# ROCKCHIP_PWR_SUPPLY.net
KiCad netlist of a schematic drawn in Altium Designer
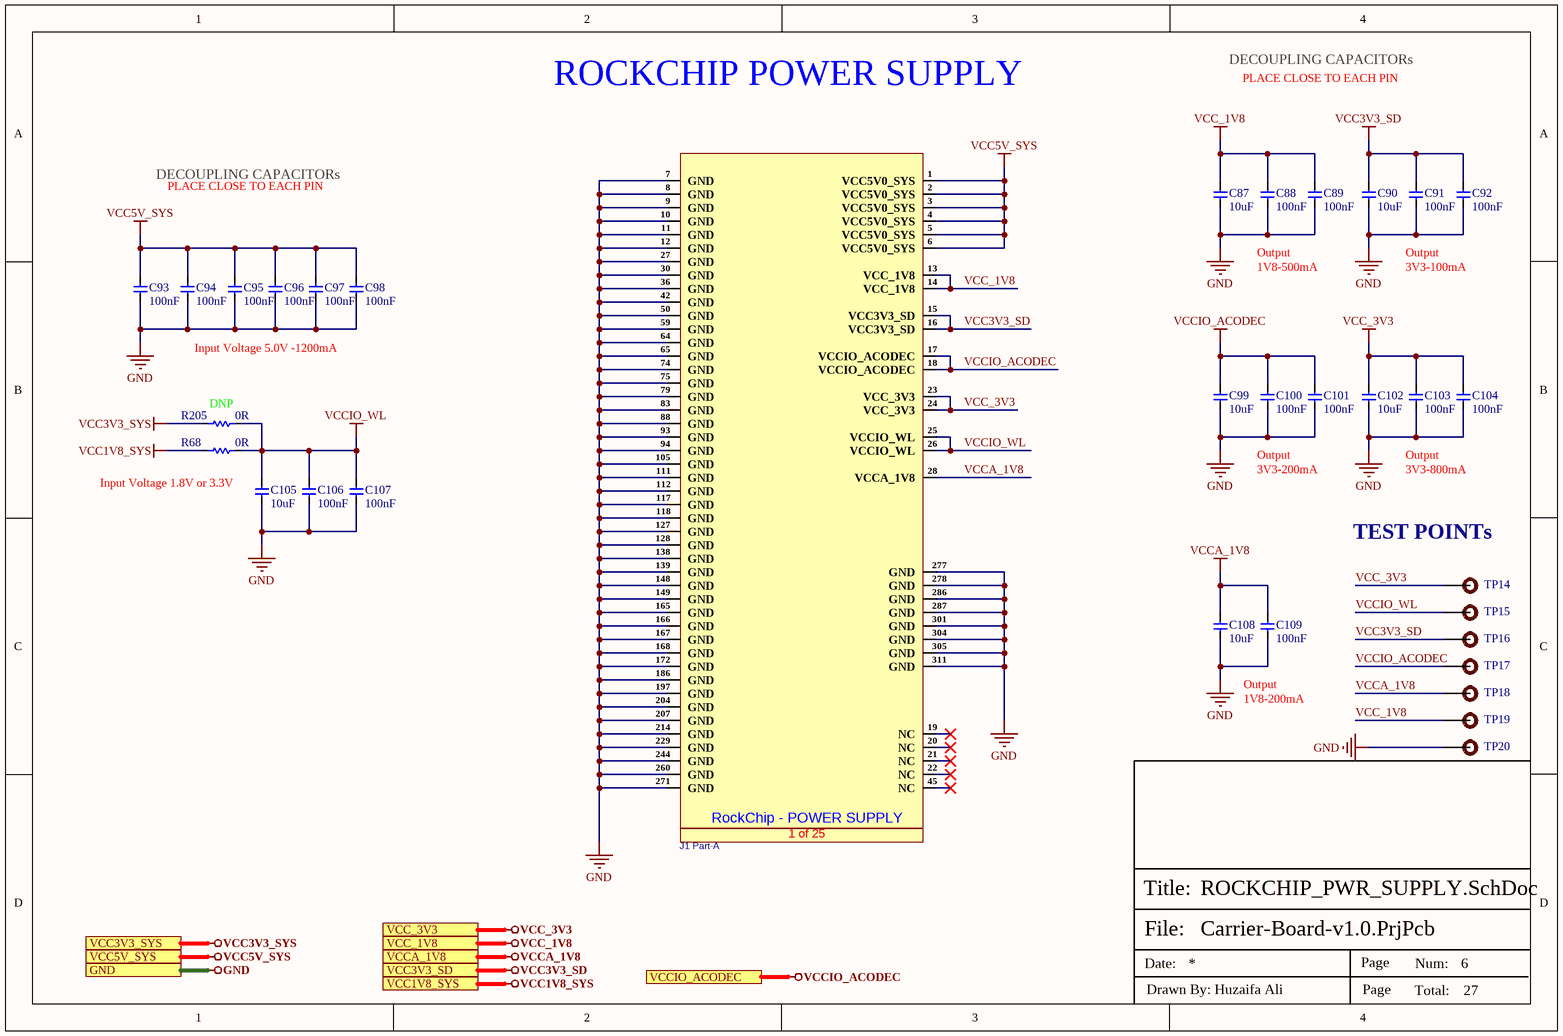
[diagram p0: ROCKCHIP_PWR_SUPPLY.SchDoc]

(export (version "E")
  (design (tool "Eeschema 10.0.6"))
  (components
    (comp (ref "C87")
      (value "10uF")
      (footprint "Cap-0603")
      (description "CAP CER 10UF 25V X5R 0603")
      (fields
        (field (name "MANUFACTURER") "TDK")
        (field (name "MANUFACTURER PART NUMBER") "C1608X5R1E106M080AC")
      )
      (libsource (lib "eSpark Libraries") (part "C1608X5R1E106M080AC"))
    )
    (comp (ref "C88")
      (value "100nF")
      (footprint "Cap-0402")
      (description "CAP CER 0.1UF 16V X5R 0402")
      (fields
        (field (name "MANUFACTURER") "Yageo")
        (field (name "MANUFACTURER PART NUMBER") "CC0402KRX5R7BB104")
      )
      (libsource (lib "eSpark Libraries") (part "CC0402KRX5R7BB104"))
    )
    (comp (ref "C89")
      (value "100nF")
      (footprint "Cap-0402")
      (description "CAP CER 0.1UF 16V X5R 0402")
      (fields
        (field (name "MANUFACTURER") "Yageo")
        (field (name "MANUFACTURER PART NUMBER") "CC0402KRX5R7BB104")
      )
      (libsource (lib "eSpark Libraries") (part "CC0402KRX5R7BB104"))
    )
    (comp (ref "C90")
      (value "10uF")
      (footprint "Cap-0603")
      (description "CAP CER 10UF 25V X5R 0603")
      (fields
        (field (name "MANUFACTURER") "TDK")
        (field (name "MANUFACTURER PART NUMBER") "C1608X5R1E106M080AC")
      )
      (libsource (lib "eSpark Libraries") (part "C1608X5R1E106M080AC"))
    )
    (comp (ref "C91")
      (value "100nF")
      (footprint "Cap-0402")
      (description "CAP CER 0.1UF 16V X5R 0402")
      (fields
        (field (name "MANUFACTURER") "Yageo")
        (field (name "MANUFACTURER PART NUMBER") "CC0402KRX5R7BB104")
      )
      (libsource (lib "eSpark Libraries") (part "CC0402KRX5R7BB104"))
    )
    (comp (ref "C92")
      (value "100nF")
      (footprint "Cap-0402")
      (description "CAP CER 0.1UF 16V X5R 0402")
      (fields
        (field (name "MANUFACTURER") "Yageo")
        (field (name "MANUFACTURER PART NUMBER") "CC0402KRX5R7BB104")
      )
      (libsource (lib "eSpark Libraries") (part "CC0402KRX5R7BB104"))
    )
    (comp (ref "C93")
      (value "100nF")
      (footprint "Cap-0402")
      (description "CAP CER 0.1UF 16V X5R 0402")
      (fields
        (field (name "MANUFACTURER") "Yageo")
        (field (name "MANUFACTURER PART NUMBER") "CC0402KRX5R7BB104")
      )
      (libsource (lib "eSpark Libraries") (part "CC0402KRX5R7BB104"))
    )
    (comp (ref "C94")
      (value "100nF")
      (footprint "Cap-0402")
      (description "CAP CER 0.1UF 16V X5R 0402")
      (fields
        (field (name "MANUFACTURER") "Yageo")
        (field (name "MANUFACTURER PART NUMBER") "CC0402KRX5R7BB104")
      )
      (libsource (lib "eSpark Libraries") (part "CC0402KRX5R7BB104"))
    )
    (comp (ref "C95")
      (value "100nF")
      (footprint "Cap-0402")
      (description "CAP CER 0.1UF 16V X5R 0402")
      (fields
        (field (name "MANUFACTURER") "Yageo")
        (field (name "MANUFACTURER PART NUMBER") "CC0402KRX5R7BB104")
      )
      (libsource (lib "eSpark Libraries") (part "CC0402KRX5R7BB104"))
    )
    (comp (ref "C96")
      (value "100nF")
      (footprint "Cap-0402")
      (description "CAP CER 0.1UF 16V X5R 0402")
      (fields
        (field (name "MANUFACTURER") "Yageo")
        (field (name "MANUFACTURER PART NUMBER") "CC0402KRX5R7BB104")
      )
      (libsource (lib "eSpark Libraries") (part "CC0402KRX5R7BB104"))
    )
    (comp (ref "C97")
      (value "100nF")
      (footprint "Cap-0402")
      (description "CAP CER 0.1UF 16V X5R 0402")
      (fields
        (field (name "MANUFACTURER") "Yageo")
        (field (name "MANUFACTURER PART NUMBER") "CC0402KRX5R7BB104")
      )
      (libsource (lib "eSpark Libraries") (part "CC0402KRX5R7BB104"))
    )
    (comp (ref "C98")
      (value "100nF")
      (footprint "Cap-0402")
      (description "CAP CER 0.1UF 16V X5R 0402")
      (fields
        (field (name "MANUFACTURER") "Yageo")
        (field (name "MANUFACTURER PART NUMBER") "CC0402KRX5R7BB104")
      )
      (libsource (lib "eSpark Libraries") (part "CC0402KRX5R7BB104"))
    )
    (comp (ref "C99")
      (value "10uF")
      (footprint "Cap-0603")
      (description "CAP CER 10UF 25V X5R 0603")
      (fields
        (field (name "MANUFACTURER") "TDK")
        (field (name "MANUFACTURER PART NUMBER") "C1608X5R1E106M080AC")
      )
      (libsource (lib "eSpark Libraries") (part "C1608X5R1E106M080AC"))
    )
    (comp (ref "C100")
      (value "100nF")
      (footprint "Cap-0402")
      (description "CAP CER 0.1UF 16V X5R 0402")
      (fields
        (field (name "MANUFACTURER") "Yageo")
        (field (name "MANUFACTURER PART NUMBER") "CC0402KRX5R7BB104")
      )
      (libsource (lib "eSpark Libraries") (part "CC0402KRX5R7BB104"))
    )
    (comp (ref "C101")
      (value "100nF")
      (footprint "Cap-0402")
      (description "CAP CER 0.1UF 16V X5R 0402")
      (fields
        (field (name "MANUFACTURER") "Yageo")
        (field (name "MANUFACTURER PART NUMBER") "CC0402KRX5R7BB104")
      )
      (libsource (lib "eSpark Libraries") (part "CC0402KRX5R7BB104"))
    )
    (comp (ref "C102")
      (value "10uF")
      (footprint "Cap-0603")
      (description "CAP CER 10UF 25V X5R 0603")
      (fields
        (field (name "MANUFACTURER") "TDK")
        (field (name "MANUFACTURER PART NUMBER") "C1608X5R1E106M080AC")
      )
      (libsource (lib "eSpark Libraries") (part "C1608X5R1E106M080AC"))
    )
    (comp (ref "C103")
      (value "100nF")
      (footprint "Cap-0402")
      (description "CAP CER 0.1UF 16V X5R 0402")
      (fields
        (field (name "MANUFACTURER") "Yageo")
        (field (name "MANUFACTURER PART NUMBER") "CC0402KRX5R7BB104")
      )
      (libsource (lib "eSpark Libraries") (part "CC0402KRX5R7BB104"))
    )
    (comp (ref "C104")
      (value "100nF")
      (footprint "Cap-0402")
      (description "CAP CER 0.1UF 16V X5R 0402")
      (fields
        (field (name "MANUFACTURER") "Yageo")
        (field (name "MANUFACTURER PART NUMBER") "CC0402KRX5R7BB104")
      )
      (libsource (lib "eSpark Libraries") (part "CC0402KRX5R7BB104"))
    )
    (comp (ref "C105")
      (value "10uF")
      (footprint "Cap-0603")
      (description "CAP CER 10UF 25V X5R 0603")
      (fields
        (field (name "MANUFACTURER") "TDK")
        (field (name "MANUFACTURER PART NUMBER") "C1608X5R1E106M080AC")
      )
      (libsource (lib "eSpark Libraries") (part "C1608X5R1E106M080AC"))
    )
    (comp (ref "C106")
      (value "100nF")
      (footprint "Cap-0402")
      (description "CAP CER 0.1UF 16V X5R 0402")
      (fields
        (field (name "MANUFACTURER") "Yageo")
        (field (name "MANUFACTURER PART NUMBER") "CC0402KRX5R7BB104")
      )
      (libsource (lib "eSpark Libraries") (part "CC0402KRX5R7BB104"))
    )
    (comp (ref "C107")
      (value "100nF")
      (footprint "Cap-0402")
      (description "CAP CER 0.1UF 16V X5R 0402")
      (fields
        (field (name "MANUFACTURER") "Yageo")
        (field (name "MANUFACTURER PART NUMBER") "CC0402KRX5R7BB104")
      )
      (libsource (lib "eSpark Libraries") (part "CC0402KRX5R7BB104"))
    )
    (comp (ref "C108")
      (value "10uF")
      (footprint "Cap-0603")
      (description "CAP CER 10UF 25V X5R 0603")
      (fields
        (field (name "MANUFACTURER") "TDK")
        (field (name "MANUFACTURER PART NUMBER") "C1608X5R1E106M080AC")
      )
      (libsource (lib "eSpark Libraries") (part "C1608X5R1E106M080AC"))
    )
    (comp (ref "C109")
      (value "100nF")
      (footprint "Cap-0402")
      (description "CAP CER 0.1UF 16V X5R 0402")
      (fields
        (field (name "MANUFACTURER") "Yageo")
        (field (name "MANUFACTURER PART NUMBER") "CC0402KRX5R7BB104")
      )
      (libsource (lib "eSpark Libraries") (part "CC0402KRX5R7BB104"))
    )
    (comp (ref "J1 Part-")
      (value "AS0B826-S78B-7H")
      (footprint "AS0B826-S78B-7H")
      (description "SMD,P=0.5mm,Surface Mount，Right Angle")
      (fields (field (name "LCSC PART NUMBER") "C426232") (field (name "MANUFACTURER") "FOXCONN"))
      (libsource (lib "eSpark Libraries") (part "AS0B826-S78B-7H"))
    )
    (comp (ref "R68")
      (value "0R")
      (footprint "Res-0402")
      (description "RES 0 OHM JUMPER 1/16W 0402")
      (fields
        (field (name "MANUFACTURER") "Yageo")
        (field (name "MANUFACTURER PART NUMBER") "RC0402FR-070RL")
      )
      (libsource (lib "eSpark Libraries") (part "RC0402FR-070RL"))
    )
    (comp (ref "R205")
      (value "DNP")
      (footprint "Res-0402")
      (description "RES 0 OHM JUMPER 1/16W 0402")
      (fields
        (field (name "MANUFACTURER") "Yageo")
        (field (name "MANUFACTURER PART NUMBER") "RC0402FR-070RL")
      )
      (libsource (lib "eSpark Libraries") (part "RC0402FR-070RL"))
    )
    (comp (ref "TP14")
      (value "TEST POINT 0.5mm Dia")
      (footprint "Test-point - 0.5mm")
      (description "Test Point ON")
      (libsource (lib "eSpark Libraries") (part "TEST POINT 0.5mm Dia"))
    )
    (comp (ref "TP15")
      (value "TEST POINT 0.5mm Dia")
      (footprint "Test-point - 0.5mm")
      (description "Test Point ON")
      (libsource (lib "eSpark Libraries") (part "TEST POINT 0.5mm Dia"))
    )
    (comp (ref "TP16")
      (value "TEST POINT 0.5mm Dia")
      (footprint "Test-point - 0.5mm")
      (description "Test Point ON")
      (libsource (lib "eSpark Libraries") (part "TEST POINT 0.5mm Dia"))
    )
    (comp (ref "TP17")
      (value "TEST POINT 0.5mm Dia")
      (footprint "Test-point - 0.5mm")
      (description "Test Point ON")
      (libsource (lib "eSpark Libraries") (part "TEST POINT 0.5mm Dia"))
    )
    (comp (ref "TP18")
      (value "TEST POINT 0.5mm Dia")
      (footprint "Test-point - 0.5mm")
      (description "Test Point ON")
      (libsource (lib "eSpark Libraries") (part "TEST POINT 0.5mm Dia"))
    )
    (comp (ref "TP19")
      (value "TEST POINT 0.5mm Dia")
      (footprint "Test-point - 0.5mm")
      (description "Test Point ON")
      (libsource (lib "eSpark Libraries") (part "TEST POINT 0.5mm Dia"))
    )
    (comp (ref "TP20")
      (value "TEST POINT 0.5mm Dia")
      (footprint "Test-point - 0.5mm")
      (description "Test Point ON")
      (libsource (lib "eSpark Libraries") (part "TEST POINT 0.5mm Dia"))
    )
  )
  (nets
    (net (code "1") (name "GND") (class "Default")
      (node (ref "C100") (pin "1") (pinfunction "1_1") (pintype "passive"))
      (node (ref "C101") (pin "1") (pinfunction "1_1") (pintype "passive"))
      (node (ref "C102") (pin "1") (pinfunction "1_1") (pintype "passive"))
      (node (ref "C103") (pin "1") (pinfunction "1_1") (pintype "passive"))
      (node (ref "C104") (pin "1") (pinfunction "1_1") (pintype "passive"))
      (node (ref "C105") (pin "1") (pinfunction "1_1") (pintype "passive"))
      (node (ref "C106") (pin "1") (pinfunction "1_1") (pintype "passive"))
      (node (ref "C107") (pin "1") (pinfunction "1_1") (pintype "passive"))
      (node (ref "C108") (pin "1") (pinfunction "1_1") (pintype "passive"))
      (node (ref "C109") (pin "1") (pinfunction "1_1") (pintype "passive"))
      (node (ref "C87") (pin "1") (pinfunction "1_1") (pintype "passive"))
      (node (ref "C88") (pin "1") (pinfunction "1_1") (pintype "passive"))
      (node (ref "C89") (pin "1") (pinfunction "1_1") (pintype "passive"))
      (node (ref "C90") (pin "1") (pinfunction "1_1") (pintype "passive"))
      (node (ref "C91") (pin "1") (pinfunction "1_1") (pintype "passive"))
      (node (ref "C92") (pin "1") (pinfunction "1_1") (pintype "passive"))
      (node (ref "C93") (pin "1") (pinfunction "1_1") (pintype "passive"))
      (node (ref "C94") (pin "1") (pinfunction "1_1") (pintype "passive"))
      (node (ref "C95") (pin "1") (pinfunction "1_1") (pintype "passive"))
      (node (ref "C96") (pin "1") (pinfunction "1_1") (pintype "passive"))
      (node (ref "C97") (pin "1") (pinfunction "1_1") (pintype "passive"))
      (node (ref "C98") (pin "1") (pinfunction "1_1") (pintype "passive"))
      (node (ref "C99") (pin "1") (pinfunction "1_1") (pintype "passive"))
      (node (ref "J1 Part-") (pin "10") (pinfunction "GND_10") (pintype "passive"))
      (node (ref "J1 Part-") (pin "105") (pinfunction "GND_105") (pintype "power_in"))
      (node (ref "J1 Part-") (pin "11") (pinfunction "GND_11") (pintype "power_in"))
      (node (ref "J1 Part-") (pin "111") (pinfunction "GND_111") (pintype "power_in"))
      (node (ref "J1 Part-") (pin "112") (pinfunction "GND_112") (pintype "power_in"))
      (node (ref "J1 Part-") (pin "117") (pinfunction "GND_117") (pintype "power_in"))
      (node (ref "J1 Part-") (pin "118") (pinfunction "GND_118") (pintype "power_in"))
      (node (ref "J1 Part-") (pin "12") (pinfunction "GND_12") (pintype "power_in"))
      (node (ref "J1 Part-") (pin "127") (pinfunction "GND_127") (pintype "power_in"))
      (node (ref "J1 Part-") (pin "128") (pinfunction "GND_128") (pintype "power_in"))
      (node (ref "J1 Part-") (pin "138") (pinfunction "GND_138") (pintype "power_in"))
      (node (ref "J1 Part-") (pin "139") (pinfunction "GND_139") (pintype "power_in"))
      (node (ref "J1 Part-") (pin "148") (pinfunction "GND_148") (pintype "power_in"))
      (node (ref "J1 Part-") (pin "149") (pinfunction "GND_149") (pintype "power_in"))
      (node (ref "J1 Part-") (pin "165") (pinfunction "GND_165") (pintype "power_in"))
      (node (ref "J1 Part-") (pin "166") (pinfunction "GND_166") (pintype "power_in"))
      (node (ref "J1 Part-") (pin "167") (pinfunction "GND_167") (pintype "power_in"))
      (node (ref "J1 Part-") (pin "168") (pinfunction "GND_168") (pintype "power_in"))
      (node (ref "J1 Part-") (pin "172") (pinfunction "GND_172") (pintype "power_in"))
      (node (ref "J1 Part-") (pin "186") (pinfunction "GND_186") (pintype "power_in"))
      (node (ref "J1 Part-") (pin "197") (pinfunction "GND_197") (pintype "power_in"))
      (node (ref "J1 Part-") (pin "204") (pinfunction "GND_204") (pintype "power_in"))
      (node (ref "J1 Part-") (pin "207") (pinfunction "GND_207") (pintype "power_in"))
      (node (ref "J1 Part-") (pin "214") (pinfunction "GND_214") (pintype "power_in"))
      (node (ref "J1 Part-") (pin "229") (pinfunction "GND_229") (pintype "power_in"))
      (node (ref "J1 Part-") (pin "244") (pinfunction "GND_244") (pintype "power_in"))
      (node (ref "J1 Part-") (pin "260") (pinfunction "GND_260") (pintype "power_in"))
      (node (ref "J1 Part-") (pin "27") (pinfunction "GND_27") (pintype "power_in"))
      (node (ref "J1 Part-") (pin "271") (pinfunction "GND_271") (pintype "power_in"))
      (node (ref "J1 Part-") (pin "277") (pinfunction "GND_277") (pintype "power_in"))
      (node (ref "J1 Part-") (pin "278") (pinfunction "GND_278") (pintype "power_in"))
      (node (ref "J1 Part-") (pin "286") (pinfunction "GND_286") (pintype "power_in"))
      (node (ref "J1 Part-") (pin "287") (pinfunction "GND_287") (pintype "power_in"))
      (node (ref "J1 Part-") (pin "30") (pinfunction "GND_30") (pintype "power_in"))
      (node (ref "J1 Part-") (pin "301") (pinfunction "GND_301") (pintype "power_in"))
      (node (ref "J1 Part-") (pin "304") (pinfunction "GND_304") (pintype "power_in"))
      (node (ref "J1 Part-") (pin "305") (pinfunction "GND_305") (pintype "passive"))
      (node (ref "J1 Part-") (pin "311") (pinfunction "GND_311") (pintype "power_in"))
      (node (ref "J1 Part-") (pin "36") (pinfunction "GND_36") (pintype "power_in"))
      (node (ref "J1 Part-") (pin "42") (pinfunction "GND_42") (pintype "power_in"))
      (node (ref "J1 Part-") (pin "50") (pinfunction "GND_50") (pintype "power_in"))
      (node (ref "J1 Part-") (pin "59") (pinfunction "GND_59") (pintype "power_in"))
      (node (ref "J1 Part-") (pin "64") (pinfunction "GND_64") (pintype "power_in"))
      (node (ref "J1 Part-") (pin "65") (pinfunction "GND_65") (pintype "power_in"))
      (node (ref "J1 Part-") (pin "7") (pinfunction "GND_7") (pintype "passive"))
      (node (ref "J1 Part-") (pin "74") (pinfunction "GND_74") (pintype "power_in"))
      (node (ref "J1 Part-") (pin "75") (pinfunction "GND_75") (pintype "power_in"))
      (node (ref "J1 Part-") (pin "79") (pinfunction "GND_79") (pintype "power_in"))
      (node (ref "J1 Part-") (pin "8") (pinfunction "GND_8") (pintype "passive"))
      (node (ref "J1 Part-") (pin "83") (pinfunction "GND_83") (pintype "power_in"))
      (node (ref "J1 Part-") (pin "88") (pinfunction "GND_88") (pintype "power_in"))
      (node (ref "J1 Part-") (pin "9") (pinfunction "GND_9") (pintype "passive"))
      (node (ref "J1 Part-") (pin "93") (pinfunction "GND_93") (pintype "power_in"))
      (node (ref "J1 Part-") (pin "94") (pinfunction "GND_94") (pintype "power_in"))
      (node (ref "TP20") (pin "1") (pinfunction "1_1") (pintype "passive"))
    )
    (net (code "2") (name "VCC1V8_SYS") (class "Default")
      (node (ref "R68") (pin "1") (pinfunction "1_1") (pintype "passive"))
    )
    (net (code "3") (name "VCC3V3_SD") (class "Default")
      (node (ref "C90") (pin "2") (pinfunction "2_2") (pintype "passive"))
      (node (ref "C91") (pin "2") (pinfunction "2_2") (pintype "passive"))
      (node (ref "C92") (pin "2") (pinfunction "2_2") (pintype "passive"))
      (node (ref "J1 Part-") (pin "15") (pinfunction "VCC3V3_SD_15") (pintype "passive"))
      (node (ref "J1 Part-") (pin "16") (pinfunction "VCC3V3_SD_16") (pintype "passive"))
      (node (ref "TP16") (pin "1") (pinfunction "1_1") (pintype "passive"))
    )
    (net (code "4") (name "VCC3V3_SYS") (class "Default")
      (node (ref "R205") (pin "1") (pinfunction "1_1") (pintype "passive"))
    )
    (net (code "5") (name "VCC5V_SYS") (class "Default")
      (node (ref "C93") (pin "2") (pinfunction "2_2") (pintype "passive"))
      (node (ref "C94") (pin "2") (pinfunction "2_2") (pintype "passive"))
      (node (ref "C95") (pin "2") (pinfunction "2_2") (pintype "passive"))
      (node (ref "C96") (pin "2") (pinfunction "2_2") (pintype "passive"))
      (node (ref "C97") (pin "2") (pinfunction "2_2") (pintype "passive"))
      (node (ref "C98") (pin "2") (pinfunction "2_2") (pintype "passive"))
      (node (ref "J1 Part-") (pin "1") (pinfunction "VCC5V0_SYS_1") (pintype "passive"))
      (node (ref "J1 Part-") (pin "2") (pinfunction "VCC5V0_SYS_2") (pintype "passive"))
      (node (ref "J1 Part-") (pin "3") (pinfunction "VCC5V0_SYS_3") (pintype "passive"))
      (node (ref "J1 Part-") (pin "4") (pinfunction "VCC5V0_SYS_4") (pintype "passive"))
      (node (ref "J1 Part-") (pin "5") (pinfunction "VCC5V0_SYS_5") (pintype "passive"))
      (node (ref "J1 Part-") (pin "6") (pinfunction "VCC5V0_SYS_6") (pintype "passive"))
    )
    (net (code "6") (name "VCCA_1V8") (class "Default")
      (node (ref "C108") (pin "2") (pinfunction "2_2") (pintype "passive"))
      (node (ref "C109") (pin "2") (pinfunction "2_2") (pintype "passive"))
      (node (ref "J1 Part-") (pin "28") (pinfunction "VCCA_1V8_28") (pintype "passive"))
      (node (ref "TP18") (pin "1") (pinfunction "1_1") (pintype "passive"))
    )
    (net (code "7") (name "VCCIO_ACODEC") (class "Default")
      (node (ref "C100") (pin "2") (pinfunction "2_2") (pintype "passive"))
      (node (ref "C101") (pin "2") (pinfunction "2_2") (pintype "passive"))
      (node (ref "C99") (pin "2") (pinfunction "2_2") (pintype "passive"))
      (node (ref "J1 Part-") (pin "17") (pinfunction "VCCIO_ACODEC_17") (pintype "passive"))
      (node (ref "J1 Part-") (pin "18") (pinfunction "VCCIO_ACODEC_18") (pintype "passive"))
      (node (ref "TP17") (pin "1") (pinfunction "1_1") (pintype "passive"))
    )
    (net (code "8") (name "VCCIO_WL") (class "Default")
      (node (ref "C105") (pin "2") (pinfunction "2_2") (pintype "passive"))
      (node (ref "C106") (pin "2") (pinfunction "2_2") (pintype "passive"))
      (node (ref "C107") (pin "2") (pinfunction "2_2") (pintype "passive"))
      (node (ref "J1 Part-") (pin "25") (pinfunction "VCCIO_WL_25") (pintype "passive"))
      (node (ref "J1 Part-") (pin "26") (pinfunction "VCCIO_WL_26") (pintype "passive"))
      (node (ref "R205") (pin "2") (pinfunction "2_2") (pintype "passive"))
      (node (ref "R68") (pin "2") (pinfunction "2_2") (pintype "passive"))
      (node (ref "TP15") (pin "1") (pinfunction "1_1") (pintype "passive"))
    )
    (net (code "9") (name "VCC_1V8") (class "Default")
      (node (ref "C87") (pin "2") (pinfunction "2_2") (pintype "passive"))
      (node (ref "C88") (pin "2") (pinfunction "2_2") (pintype "passive"))
      (node (ref "C89") (pin "2") (pinfunction "2_2") (pintype "passive"))
      (node (ref "J1 Part-") (pin "13") (pinfunction "VCC_1V8_13") (pintype "passive"))
      (node (ref "J1 Part-") (pin "14") (pinfunction "VCC_1V8_14") (pintype "passive"))
      (node (ref "TP19") (pin "1") (pinfunction "1_1") (pintype "passive"))
    )
    (net (code "10") (name "VCC_3V3") (class "Default")
      (node (ref "C102") (pin "2") (pinfunction "2_2") (pintype "passive"))
      (node (ref "C103") (pin "2") (pinfunction "2_2") (pintype "passive"))
      (node (ref "C104") (pin "2") (pinfunction "2_2") (pintype "passive"))
      (node (ref "J1 Part-") (pin "23") (pinfunction "VCC_3V3_23") (pintype "passive"))
      (node (ref "J1 Part-") (pin "24") (pinfunction "VCC_3V3_24") (pintype "passive"))
      (node (ref "TP14") (pin "1") (pinfunction "1_1") (pintype "passive"))
    )
    (net (code "11") (name "unconnected-(J1 Part-A-NC-Pad19)") (class "Default")
      (node (ref "J1 Part-") (pin "19") (pinfunction "NC_19") (pintype "passive+no_connect"))
    )
    (net (code "12") (name "unconnected-(J1 Part-A-NC-Pad20)") (class "Default")
      (node (ref "J1 Part-") (pin "20") (pinfunction "NC_20") (pintype "passive+no_connect"))
    )
    (net (code "13") (name "unconnected-(J1 Part-A-NC-Pad21)") (class "Default")
      (node (ref "J1 Part-") (pin "21") (pinfunction "NC_21") (pintype "passive+no_connect"))
    )
    (net (code "14") (name "unconnected-(J1 Part-A-NC-Pad22)") (class "Default")
      (node (ref "J1 Part-") (pin "22") (pinfunction "NC_22") (pintype "passive+no_connect"))
    )
    (net (code "15") (name "unconnected-(J1 Part-A-NC-Pad45)") (class "Default")
      (node (ref "J1 Part-") (pin "45") (pinfunction "NC_45") (pintype "passive+no_connect"))
    )
  )
)
